# Nyan.net
KiCad netlist of a schematic drawn in EAGLE
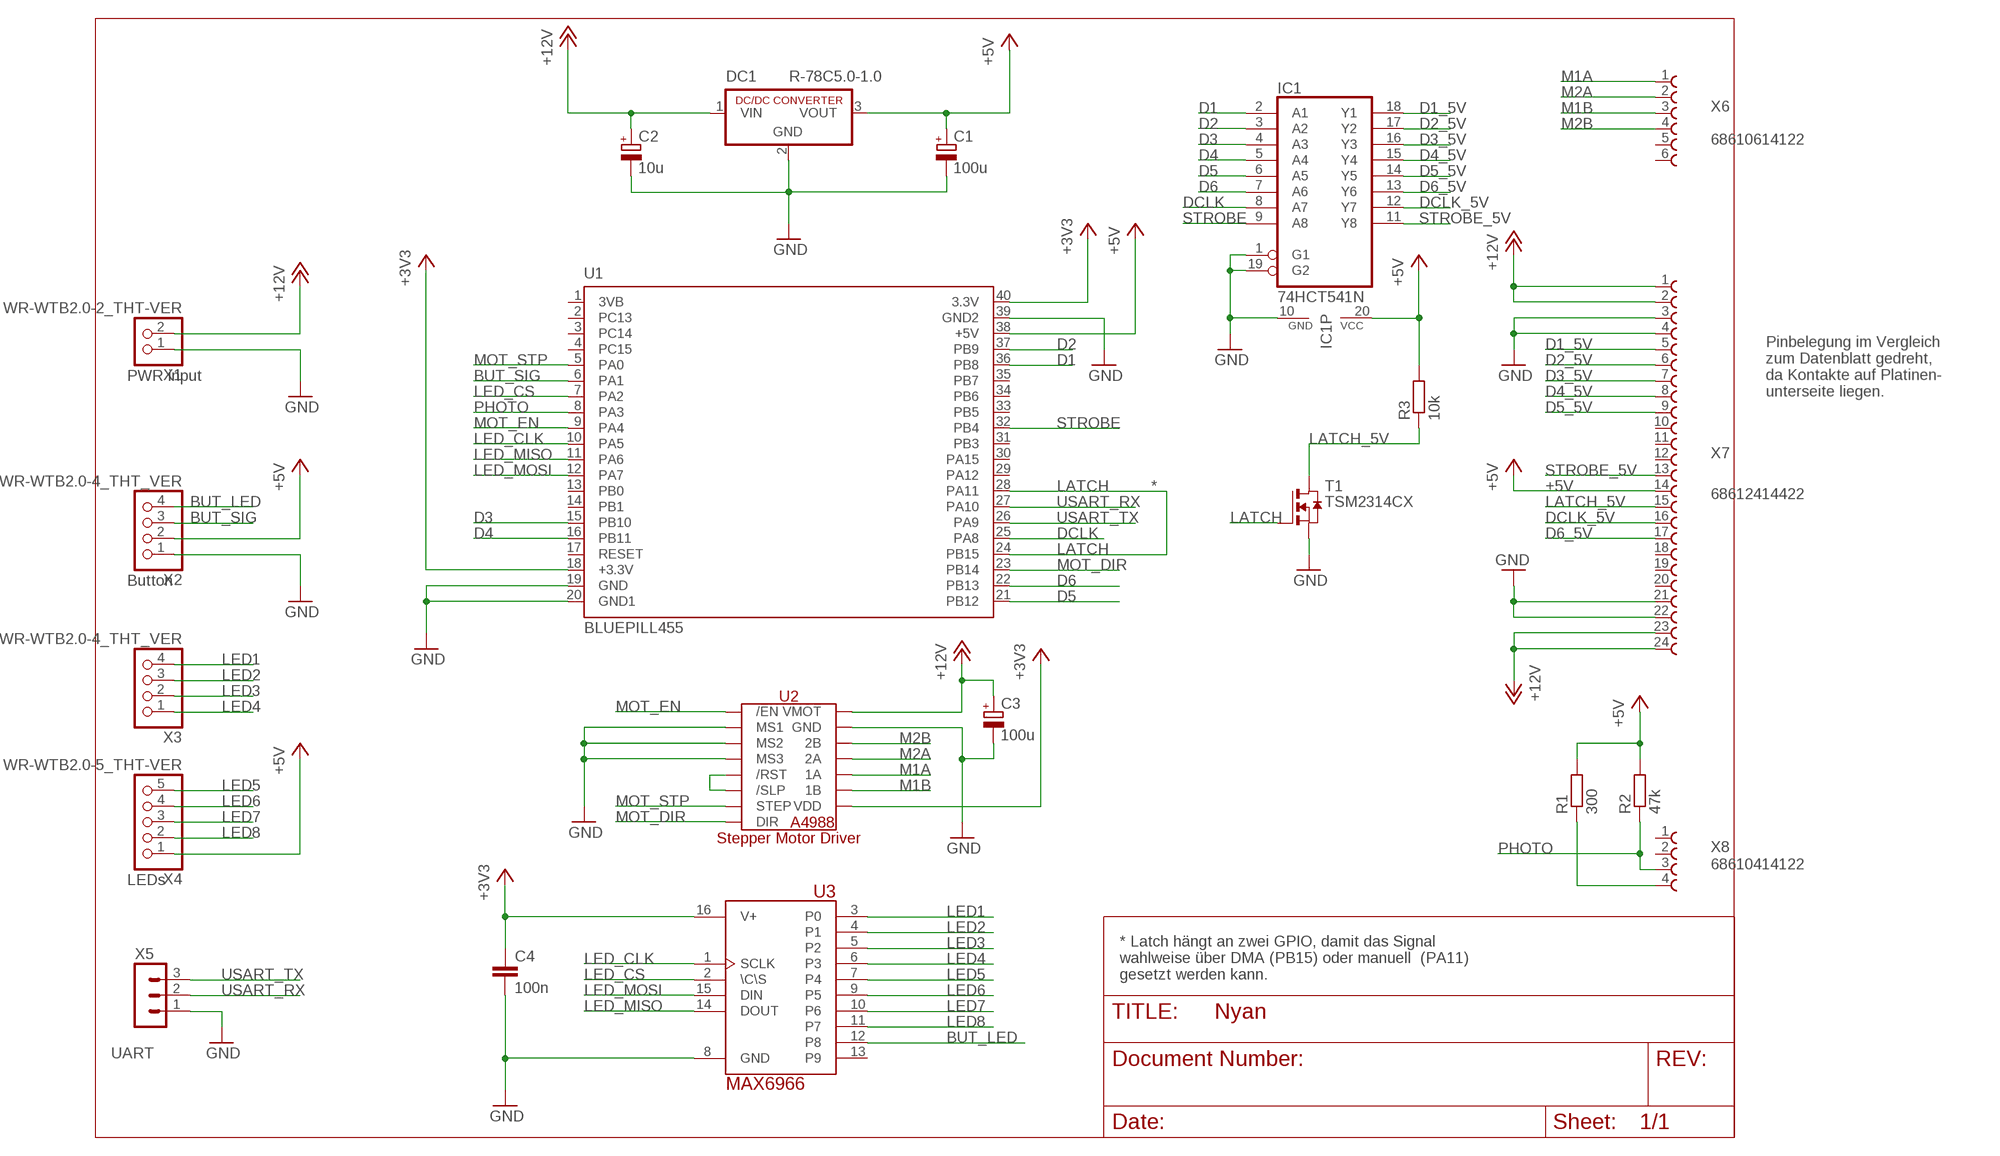
[diagram p0: schematic, sheet 1]

(export (version "E")
  (design (tool "Eeschema 10.0.6"))
  (components
    (comp (ref "C1")
      (value "100u")
      (footprint "eagle-import:E2,5-6")
      (libsource (lib "eagle-import") (part "CPOL-EUE2.5-6"))
    )
    (comp (ref "C2")
      (value "10u")
      (footprint "eagle-import:E2,5-6")
      (libsource (lib "eagle-import") (part "CPOL-EUE2.5-6"))
    )
    (comp (ref "C3")
      (value "100u")
      (footprint "eagle-import:E2,5-6")
      (libsource (lib "eagle-import") (part "CPOL-EUE2.5-6"))
    )
    (comp (ref "C4")
      (value "100n")
      (footprint "eagle-import:C075-032X103")
      (libsource (lib "eagle-import") (part "C-EU075-032X103"))
    )
    (comp (ref "DC1")
      (value "R-78C5.0-1.0")
      (footprint "eagle-import:SIP3")
      (libsource (lib "eagle-import") (part "R-78C-1.05.0"))
    )
    (comp (ref "IC1")
      (value "74HCT541N")
      (footprint "eagle-import:DIL20")
      (libsource (lib "eagle-import") (part "74541NHCT"))
    )
    (comp (ref "R1")
      (value "300")
      (footprint "eagle-import:0204_7")
      (libsource (lib "eagle-import") (part "R-EU_0204/7"))
    )
    (comp (ref "R2")
      (value "47k")
      (footprint "eagle-import:0204_7")
      (libsource (lib "eagle-import") (part "R-EU_0204/7"))
    )
    (comp (ref "R3")
      (value "10k")
      (footprint "eagle-import:R0603")
      (libsource (lib "eagle-import") (part "R-EU_R0603"))
    )
    (comp (ref "T1")
      (value "TSM2314CX")
      (footprint "eagle-import:SOT-23")
      (libsource (lib "eagle-import") (part "TSM2314CX"))
    )
    (comp (ref "U1")
      (value "BLUEPILL455")
      (footprint "eagle-import:DIL40")
      (fields (field (name "MF") "BluePill"))
      (libsource (lib "eagle-import") (part "BLUEPILL455"))
    )
    (comp (ref "U2")
      (value "A4988_STEP")
      (footprint "eagle-import:A4988_STEP")
      (libsource (lib "eagle-import") (part "A4988_STEP"))
    )
    (comp (ref "U3")
      (value "MAX6966")
      (footprint "eagle-import:QSOP-16")
      (libsource (lib "eagle-import") (part "MAX6966"))
    )
    (comp (ref "X1")
      (value "WR-WTB2.0-2_THT-VER")
      (footprint "eagle-import:WR-WTB2.0-2-THT-VER")
      (libsource (lib "eagle-import") (part "WR-WTB2.0-2_THT-VER"))
    )
    (comp (ref "X2")
      (value "WR-WTB2.0-4_THT_VER")
      (footprint "eagle-import:WR-WTB2.0-4-THT-VER")
      (libsource (lib "eagle-import") (part "WR-WTB2.0-4_THT_VER"))
    )
    (comp (ref "X3")
      (value "WR-WTB2.0-4_THT_VER")
      (footprint "eagle-import:WR-WTB2.0-4-THT-VER")
      (libsource (lib "eagle-import") (part "WR-WTB2.0-4_THT_VER"))
    )
    (comp (ref "X4")
      (value "WR-WTB2.0-5_THT-VER")
      (footprint "eagle-import:WR-WTB2.0-5-THT-VER")
      (libsource (lib "eagle-import") (part "WR-WTB2.0-5_THT-VER"))
    )
    (comp (ref "X5")
      (value "MA03-1ROUND_PAD")
      (footprint "eagle-import:MA03-1_ROUND")
      (libsource (lib "eagle-import") (part "MA03-1ROUND_PAD"))
    )
    (comp (ref "X6")
      (value "68610614122")
      (footprint "eagle-import:68610614122")
      (libsource (lib "eagle-import") (part "68610614122"))
    )
    (comp (ref "X7")
      (value "68612414422")
      (footprint "eagle-import:68612414422")
      (libsource (lib "eagle-import") (part "68612414422"))
    )
    (comp (ref "X8")
      (value "68610414122")
      (footprint "eagle-import:68610414122")
      (libsource (lib "eagle-import") (part "68610414122"))
    )
  )
  (nets
    (net (code "1") (name "+3V3") (class "Default")
      (node (ref "C4") (pin "1") (pinfunction "1_1") (pintype "passive"))
      (node (ref "U1") (pin "18") (pinfunction "+3.3V_18") (pintype "bidirectional"))
      (node (ref "U1") (pin "40") (pinfunction "3.3V_40") (pintype "bidirectional"))
      (node (ref "U2") (pin "VDD") (pinfunction "VDD_VDD") (pintype "bidirectional"))
      (node (ref "U3") (pin "16") (pinfunction "V+_16") (pintype "power_in"))
    )
    (net (code "2") (name "+5V") (class "Default")
      (node (ref "C1") (pin "+") (pinfunction "+_+") (pintype "passive"))
      (node (ref "DC1") (pin "3") (pinfunction "VOUT_3") (pintype "passive"))
      (node (ref "IC1") (pin "20") (pinfunction "VCC_20") (pintype "power_in"))
      (node (ref "R1") (pin "2") (pinfunction "2_2") (pintype "passive"))
      (node (ref "R2") (pin "2") (pinfunction "2_2") (pintype "passive"))
      (node (ref "R3") (pin "2") (pinfunction "2_2") (pintype "passive"))
      (node (ref "U1") (pin "38") (pinfunction "+5V_38") (pintype "bidirectional"))
      (node (ref "X2") (pin "2") (pinfunction "2_2") (pintype "passive"))
      (node (ref "X4") (pin "1") (pinfunction "1_1") (pintype "passive"))
      (node (ref "X7") (pin "14") (pinfunction "14_14") (pintype "passive"))
    )
    (net (code "3") (name "+12V") (class "Default")
      (node (ref "C2") (pin "+") (pinfunction "+_+") (pintype "passive"))
      (node (ref "C3") (pin "+") (pinfunction "+_+") (pintype "passive"))
      (node (ref "DC1") (pin "1") (pinfunction "VIN_1") (pintype "passive"))
      (node (ref "U2") (pin "VMOT") (pinfunction "VMOT_VMOT") (pintype "bidirectional"))
      (node (ref "X1") (pin "2") (pinfunction "2_2") (pintype "passive"))
      (node (ref "X7") (pin "1") (pinfunction "1_1") (pintype "passive"))
      (node (ref "X7") (pin "2") (pinfunction "2_2") (pintype "passive"))
      (node (ref "X7") (pin "23") (pinfunction "23_23") (pintype "passive"))
      (node (ref "X7") (pin "24") (pinfunction "24_24") (pintype "passive"))
    )
    (net (code "4") (name "/BUT_LED") (class "Default")
      (node (ref "U3") (pin "12") (pinfunction "P8_12") (pintype "bidirectional"))
      (node (ref "X2") (pin "4") (pinfunction "4_4") (pintype "passive"))
    )
    (net (code "5") (name "/BUT_SIG") (class "Default")
      (node (ref "U1") (pin "6") (pinfunction "PA1_6") (pintype "bidirectional"))
      (node (ref "X2") (pin "3") (pinfunction "3_3") (pintype "passive"))
    )
    (net (code "6") (name "/D1") (class "Default")
      (node (ref "IC1") (pin "2") (pinfunction "A1_2") (pintype "input"))
      (node (ref "U1") (pin "36") (pinfunction "PB8_36") (pintype "bidirectional"))
    )
    (net (code "7") (name "/D1_5V") (class "Default")
      (node (ref "IC1") (pin "18") (pinfunction "Y1_18") (pintype "tri_state"))
      (node (ref "X7") (pin "5") (pinfunction "5_5") (pintype "passive"))
    )
    (net (code "8") (name "/D2") (class "Default")
      (node (ref "IC1") (pin "3") (pinfunction "A2_3") (pintype "input"))
      (node (ref "U1") (pin "37") (pinfunction "PB9_37") (pintype "bidirectional"))
    )
    (net (code "9") (name "/D2_5V") (class "Default")
      (node (ref "IC1") (pin "17") (pinfunction "Y2_17") (pintype "tri_state"))
      (node (ref "X7") (pin "6") (pinfunction "6_6") (pintype "passive"))
    )
    (net (code "10") (name "/D3") (class "Default")
      (node (ref "IC1") (pin "4") (pinfunction "A3_4") (pintype "input"))
      (node (ref "U1") (pin "15") (pinfunction "PB10_15") (pintype "bidirectional"))
    )
    (net (code "11") (name "/D3_5V") (class "Default")
      (node (ref "IC1") (pin "16") (pinfunction "Y3_16") (pintype "tri_state"))
      (node (ref "X7") (pin "7") (pinfunction "7_7") (pintype "passive"))
    )
    (net (code "12") (name "/D4") (class "Default")
      (node (ref "IC1") (pin "5") (pinfunction "A4_5") (pintype "input"))
      (node (ref "U1") (pin "16") (pinfunction "PB11_16") (pintype "bidirectional"))
    )
    (net (code "13") (name "/D4_5V") (class "Default")
      (node (ref "IC1") (pin "15") (pinfunction "Y4_15") (pintype "tri_state"))
      (node (ref "X7") (pin "8") (pinfunction "8_8") (pintype "passive"))
    )
    (net (code "14") (name "/D5") (class "Default")
      (node (ref "IC1") (pin "6") (pinfunction "A5_6") (pintype "input"))
      (node (ref "U1") (pin "21") (pinfunction "PB12_21") (pintype "bidirectional"))
    )
    (net (code "15") (name "/D5_5V") (class "Default")
      (node (ref "IC1") (pin "14") (pinfunction "Y5_14") (pintype "tri_state"))
      (node (ref "X7") (pin "9") (pinfunction "9_9") (pintype "passive"))
    )
    (net (code "16") (name "/D6") (class "Default")
      (node (ref "IC1") (pin "7") (pinfunction "A6_7") (pintype "input"))
      (node (ref "U1") (pin "22") (pinfunction "PB13_22") (pintype "bidirectional"))
    )
    (net (code "17") (name "/D6_5V") (class "Default")
      (node (ref "IC1") (pin "13") (pinfunction "Y6_13") (pintype "tri_state"))
      (node (ref "X7") (pin "17") (pinfunction "17_17") (pintype "passive"))
    )
    (net (code "18") (name "/DCLK") (class "Default")
      (node (ref "IC1") (pin "8") (pinfunction "A7_8") (pintype "input"))
      (node (ref "U1") (pin "25") (pinfunction "PA8_25") (pintype "bidirectional"))
    )
    (net (code "19") (name "/DCLK_5V") (class "Default")
      (node (ref "IC1") (pin "12") (pinfunction "Y7_12") (pintype "tri_state"))
      (node (ref "X7") (pin "16") (pinfunction "16_16") (pintype "passive"))
    )
    (net (code "20") (name "/LATCH") (class "Default")
      (node (ref "T1") (pin "1") (pinfunction "G_1") (pintype "passive"))
      (node (ref "U1") (pin "24") (pinfunction "PB15_24") (pintype "bidirectional"))
      (node (ref "U1") (pin "28") (pinfunction "PA11_28") (pintype "bidirectional"))
    )
    (net (code "21") (name "/LATCH_5V") (class "Default")
      (node (ref "R3") (pin "1") (pinfunction "1_1") (pintype "passive"))
      (node (ref "T1") (pin "3") (pinfunction "D_3") (pintype "passive"))
      (node (ref "X7") (pin "15") (pinfunction "15_15") (pintype "passive"))
    )
    (net (code "22") (name "/LED1") (class "Default")
      (node (ref "U3") (pin "3") (pinfunction "P0_3") (pintype "bidirectional"))
      (node (ref "X3") (pin "4") (pinfunction "4_4") (pintype "passive"))
    )
    (net (code "23") (name "/LED2") (class "Default")
      (node (ref "U3") (pin "4") (pinfunction "P1_4") (pintype "bidirectional"))
      (node (ref "X3") (pin "3") (pinfunction "3_3") (pintype "passive"))
    )
    (net (code "24") (name "/LED3") (class "Default")
      (node (ref "U3") (pin "5") (pinfunction "P2_5") (pintype "bidirectional"))
      (node (ref "X3") (pin "2") (pinfunction "2_2") (pintype "passive"))
    )
    (net (code "25") (name "/LED4") (class "Default")
      (node (ref "U3") (pin "6") (pinfunction "P3_6") (pintype "bidirectional"))
      (node (ref "X3") (pin "1") (pinfunction "1_1") (pintype "passive"))
    )
    (net (code "26") (name "/LED5") (class "Default")
      (node (ref "U3") (pin "7") (pinfunction "P4_7") (pintype "bidirectional"))
      (node (ref "X4") (pin "5") (pinfunction "5_5") (pintype "passive"))
    )
    (net (code "27") (name "/LED6") (class "Default")
      (node (ref "U3") (pin "9") (pinfunction "P5_9") (pintype "bidirectional"))
      (node (ref "X4") (pin "4") (pinfunction "4_4") (pintype "passive"))
    )
    (net (code "28") (name "/LED7") (class "Default")
      (node (ref "U3") (pin "10") (pinfunction "P6_10") (pintype "bidirectional"))
      (node (ref "X4") (pin "3") (pinfunction "3_3") (pintype "passive"))
    )
    (net (code "29") (name "/LED8") (class "Default")
      (node (ref "U3") (pin "11") (pinfunction "P7_11") (pintype "bidirectional"))
      (node (ref "X4") (pin "2") (pinfunction "2_2") (pintype "passive"))
    )
    (net (code "30") (name "/LED_CLK") (class "Default")
      (node (ref "U1") (pin "10") (pinfunction "PA5_10") (pintype "bidirectional"))
      (node (ref "U3") (pin "1") (pinfunction "SCLK_1") (pintype "input"))
    )
    (net (code "31") (name "/LED_CS") (class "Default")
      (node (ref "U1") (pin "7") (pinfunction "PA2_7") (pintype "bidirectional"))
      (node (ref "U3") (pin "2") (pinfunction "\\C\\S_2") (pintype "input"))
    )
    (net (code "32") (name "/LED_MISO") (class "Default")
      (node (ref "U1") (pin "11") (pinfunction "PA6_11") (pintype "power_in"))
      (node (ref "U3") (pin "14") (pinfunction "DOUT_14") (pintype "output"))
    )
    (net (code "33") (name "/LED_MOSI") (class "Default")
      (node (ref "U1") (pin "12") (pinfunction "PA7_12") (pintype "power_in"))
      (node (ref "U3") (pin "15") (pinfunction "DIN_15") (pintype "input"))
    )
    (net (code "34") (name "/M1A") (class "Default")
      (node (ref "U2") (pin "1A") (pinfunction "1A_1A") (pintype "bidirectional"))
      (node (ref "X6") (pin "1") (pinfunction "1_1") (pintype "passive"))
    )
    (net (code "35") (name "/M1B") (class "Default")
      (node (ref "U2") (pin "1B") (pinfunction "1B_1B") (pintype "bidirectional"))
      (node (ref "X6") (pin "3") (pinfunction "3_3") (pintype "passive"))
    )
    (net (code "36") (name "/M2A") (class "Default")
      (node (ref "U2") (pin "2A") (pinfunction "2A_2A") (pintype "bidirectional"))
      (node (ref "X6") (pin "2") (pinfunction "2_2") (pintype "passive"))
    )
    (net (code "37") (name "/M2B") (class "Default")
      (node (ref "U2") (pin "2B") (pinfunction "2B_2B") (pintype "bidirectional"))
      (node (ref "X6") (pin "4") (pinfunction "4_4") (pintype "passive"))
    )
    (net (code "38") (name "/MOT_DIR") (class "Default")
      (node (ref "U1") (pin "23") (pinfunction "PB14_23") (pintype "bidirectional"))
      (node (ref "U2") (pin "DIR") (pinfunction "DIR_DIR") (pintype "bidirectional"))
    )
    (net (code "39") (name "/MOT_EN") (class "Default")
      (node (ref "U1") (pin "9") (pinfunction "PA4_9") (pintype "bidirectional"))
      (node (ref "U2") (pin "/EN") (pinfunction "/EN_/EN") (pintype "bidirectional"))
    )
    (net (code "40") (name "/MOT_STP") (class "Default")
      (node (ref "U1") (pin "5") (pinfunction "PA0_5") (pintype "bidirectional"))
      (node (ref "U2") (pin "STEP") (pinfunction "STEP_STEP") (pintype "bidirectional"))
    )
    (net (code "41") (name "/PB3") (class "Default")
      (node (ref "U1") (pin "31") (pinfunction "PB3_31") (pintype "power_in"))
    )
    (net (code "42") (name "/PHOTO") (class "Default")
      (node (ref "R2") (pin "1") (pinfunction "1_1") (pintype "passive"))
      (node (ref "U1") (pin "8") (pinfunction "PA3_8") (pintype "bidirectional"))
      (node (ref "X8") (pin "3") (pinfunction "3_3") (pintype "passive"))
    )
    (net (code "43") (name "/STROBE") (class "Default")
      (node (ref "IC1") (pin "9") (pinfunction "A8_9") (pintype "input"))
      (node (ref "U1") (pin "32") (pinfunction "PB4_32") (pintype "power_in"))
    )
    (net (code "44") (name "/STROBE_5V") (class "Default")
      (node (ref "IC1") (pin "11") (pinfunction "Y8_11") (pintype "tri_state"))
      (node (ref "X7") (pin "13") (pinfunction "13_13") (pintype "passive"))
    )
    (net (code "45") (name "/USART_RX") (class "Default")
      (node (ref "U1") (pin "27") (pinfunction "PA10_27") (pintype "bidirectional"))
      (node (ref "X5") (pin "2") (pinfunction "2_2") (pintype "passive"))
    )
    (net (code "46") (name "/USART_TX") (class "Default")
      (node (ref "U1") (pin "26") (pinfunction "PA9_26") (pintype "bidirectional"))
      (node (ref "X5") (pin "3") (pinfunction "3_3") (pintype "passive"))
    )
    (net (code "47") (name "GND") (class "Default")
      (node (ref "C1") (pin "-") (pinfunction "-_-") (pintype "passive"))
      (node (ref "C2") (pin "-") (pinfunction "-_-") (pintype "passive"))
      (node (ref "C3") (pin "-") (pinfunction "-_-") (pintype "passive"))
      (node (ref "C4") (pin "2") (pinfunction "2_2") (pintype "passive"))
      (node (ref "DC1") (pin "2") (pinfunction "GND_2") (pintype "passive"))
      (node (ref "IC1") (pin "1") (pinfunction "G1_1") (pintype "input"))
      (node (ref "IC1") (pin "10") (pinfunction "GND_10") (pintype "power_in"))
      (node (ref "IC1") (pin "19") (pinfunction "G2_19") (pintype "input"))
      (node (ref "T1") (pin "2") (pinfunction "S_2") (pintype "passive"))
      (node (ref "U1") (pin "19") (pinfunction "GND_19") (pintype "bidirectional"))
      (node (ref "U1") (pin "20") (pinfunction "GND1_20") (pintype "bidirectional"))
      (node (ref "U1") (pin "39") (pinfunction "GND2_39") (pintype "bidirectional"))
      (node (ref "U2") (pin "GND") (pinfunction "GND_GND") (pintype "bidirectional"))
      (node (ref "U2") (pin "GND2") (pinfunction "GND_GND2") (pintype "bidirectional"))
      (node (ref "U2") (pin "MS1") (pinfunction "MS1_MS1") (pintype "bidirectional"))
      (node (ref "U2") (pin "MS2") (pinfunction "MS2_MS2") (pintype "bidirectional"))
      (node (ref "U2") (pin "MS3") (pinfunction "MS3_MS3") (pintype "bidirectional"))
      (node (ref "U3") (pin "8") (pinfunction "GND_8") (pintype "power_in"))
      (node (ref "X1") (pin "1") (pinfunction "1_1") (pintype "passive"))
      (node (ref "X2") (pin "1") (pinfunction "1_1") (pintype "passive"))
      (node (ref "X5") (pin "1") (pinfunction "1_1") (pintype "passive"))
      (node (ref "X7") (pin "21") (pinfunction "21_21") (pintype "passive"))
      (node (ref "X7") (pin "22") (pinfunction "22_22") (pintype "passive"))
      (node (ref "X7") (pin "3") (pinfunction "3_3") (pintype "passive"))
      (node (ref "X7") (pin "4") (pinfunction "4_4") (pintype "passive"))
    )
    (net (code "48") (name "Net-(R1-Pad1)") (class "Default")
      (node (ref "R1") (pin "1") (pinfunction "1_1") (pintype "passive"))
      (node (ref "X8") (pin "4") (pinfunction "4_4") (pintype "passive"))
    )
    (net (code "49") (name "Net-(U2-Pad{slash}RST)") (class "Default")
      (node (ref "U2") (pin "/RST") (pinfunction "/RST_/RST") (pintype "bidirectional"))
      (node (ref "U2") (pin "/SLP") (pinfunction "/SLP_/SLP") (pintype "bidirectional"))
    )
    (net (code "50") (name "unconnected-(U1-3VB-Pad1)") (class "Default")
      (node (ref "U1") (pin "1") (pinfunction "3VB_1") (pintype "input"))
    )
    (net (code "51") (name "unconnected-(U1-PA12-Pad29)") (class "Default")
      (node (ref "U1") (pin "29") (pinfunction "PA12_29") (pintype "bidirectional"))
    )
    (net (code "52") (name "unconnected-(U1-PA15-Pad30)") (class "Default")
      (node (ref "U1") (pin "30") (pinfunction "PA15_30") (pintype "bidirectional"))
    )
    (net (code "53") (name "unconnected-(U1-PB0-Pad13)") (class "Default")
      (node (ref "U1") (pin "13") (pinfunction "PB0_13") (pintype "input"))
    )
    (net (code "54") (name "unconnected-(U1-PB1-Pad14)") (class "Default")
      (node (ref "U1") (pin "14") (pinfunction "PB1_14") (pintype "output"))
    )
    (net (code "55") (name "unconnected-(U1-PB5-Pad33)") (class "Default")
      (node (ref "U1") (pin "33") (pinfunction "PB5_33") (pintype "bidirectional"))
    )
    (net (code "56") (name "unconnected-(U1-PB6-Pad34)") (class "Default")
      (node (ref "U1") (pin "34") (pinfunction "PB6_34") (pintype "bidirectional"))
    )
    (net (code "57") (name "unconnected-(U1-PB7-Pad35)") (class "Default")
      (node (ref "U1") (pin "35") (pinfunction "PB7_35") (pintype "bidirectional"))
    )
    (net (code "58") (name "unconnected-(U1-PC13-Pad2)") (class "Default")
      (node (ref "U1") (pin "2") (pinfunction "PC13_2") (pintype "bidirectional"))
    )
    (net (code "59") (name "unconnected-(U1-PC14-Pad3)") (class "Default")
      (node (ref "U1") (pin "3") (pinfunction "PC14_3") (pintype "bidirectional"))
    )
    (net (code "60") (name "unconnected-(U1-PC15-Pad4)") (class "Default")
      (node (ref "U1") (pin "4") (pinfunction "PC15_4") (pintype "bidirectional"))
    )
    (net (code "61") (name "unconnected-(U1-RESET-Pad17)") (class "Default")
      (node (ref "U1") (pin "17") (pinfunction "RESET_17") (pintype "bidirectional"))
    )
    (net (code "62") (name "unconnected-(U3-P9-Pad13)") (class "Default")
      (node (ref "U3") (pin "13") (pinfunction "P9_13") (pintype "bidirectional"))
    )
    (net (code "63") (name "unconnected-(X6-Pad5)") (class "Default")
      (node (ref "X6") (pin "5") (pinfunction "5_5") (pintype "passive"))
    )
    (net (code "64") (name "unconnected-(X6-Pad6)") (class "Default")
      (node (ref "X6") (pin "6") (pinfunction "6_6") (pintype "passive"))
    )
    (net (code "65") (name "unconnected-(X7-Pad10)") (class "Default")
      (node (ref "X7") (pin "10") (pinfunction "10_10") (pintype "passive"))
    )
    (net (code "66") (name "unconnected-(X7-Pad11)") (class "Default")
      (node (ref "X7") (pin "11") (pinfunction "11_11") (pintype "passive"))
    )
    (net (code "67") (name "unconnected-(X7-Pad12)") (class "Default")
      (node (ref "X7") (pin "12") (pinfunction "12_12") (pintype "passive"))
    )
    (net (code "68") (name "unconnected-(X7-Pad18)") (class "Default")
      (node (ref "X7") (pin "18") (pinfunction "18_18") (pintype "passive"))
    )
    (net (code "69") (name "unconnected-(X7-Pad19)") (class "Default")
      (node (ref "X7") (pin "19") (pinfunction "19_19") (pintype "passive"))
    )
    (net (code "70") (name "unconnected-(X7-Pad20)") (class "Default")
      (node (ref "X7") (pin "20") (pinfunction "20_20") (pintype "passive"))
    )
    (net (code "71") (name "unconnected-(X8-Pad1)") (class "Default")
      (node (ref "X8") (pin "1") (pinfunction "1_1") (pintype "passive"))
    )
    (net (code "72") (name "unconnected-(X8-Pad2)") (class "Default")
      (node (ref "X8") (pin "2") (pinfunction "2_2") (pintype "passive"))
    )
  )
)
